# Top_Level.net
KiCad netlist of a schematic drawn in Altium Designer
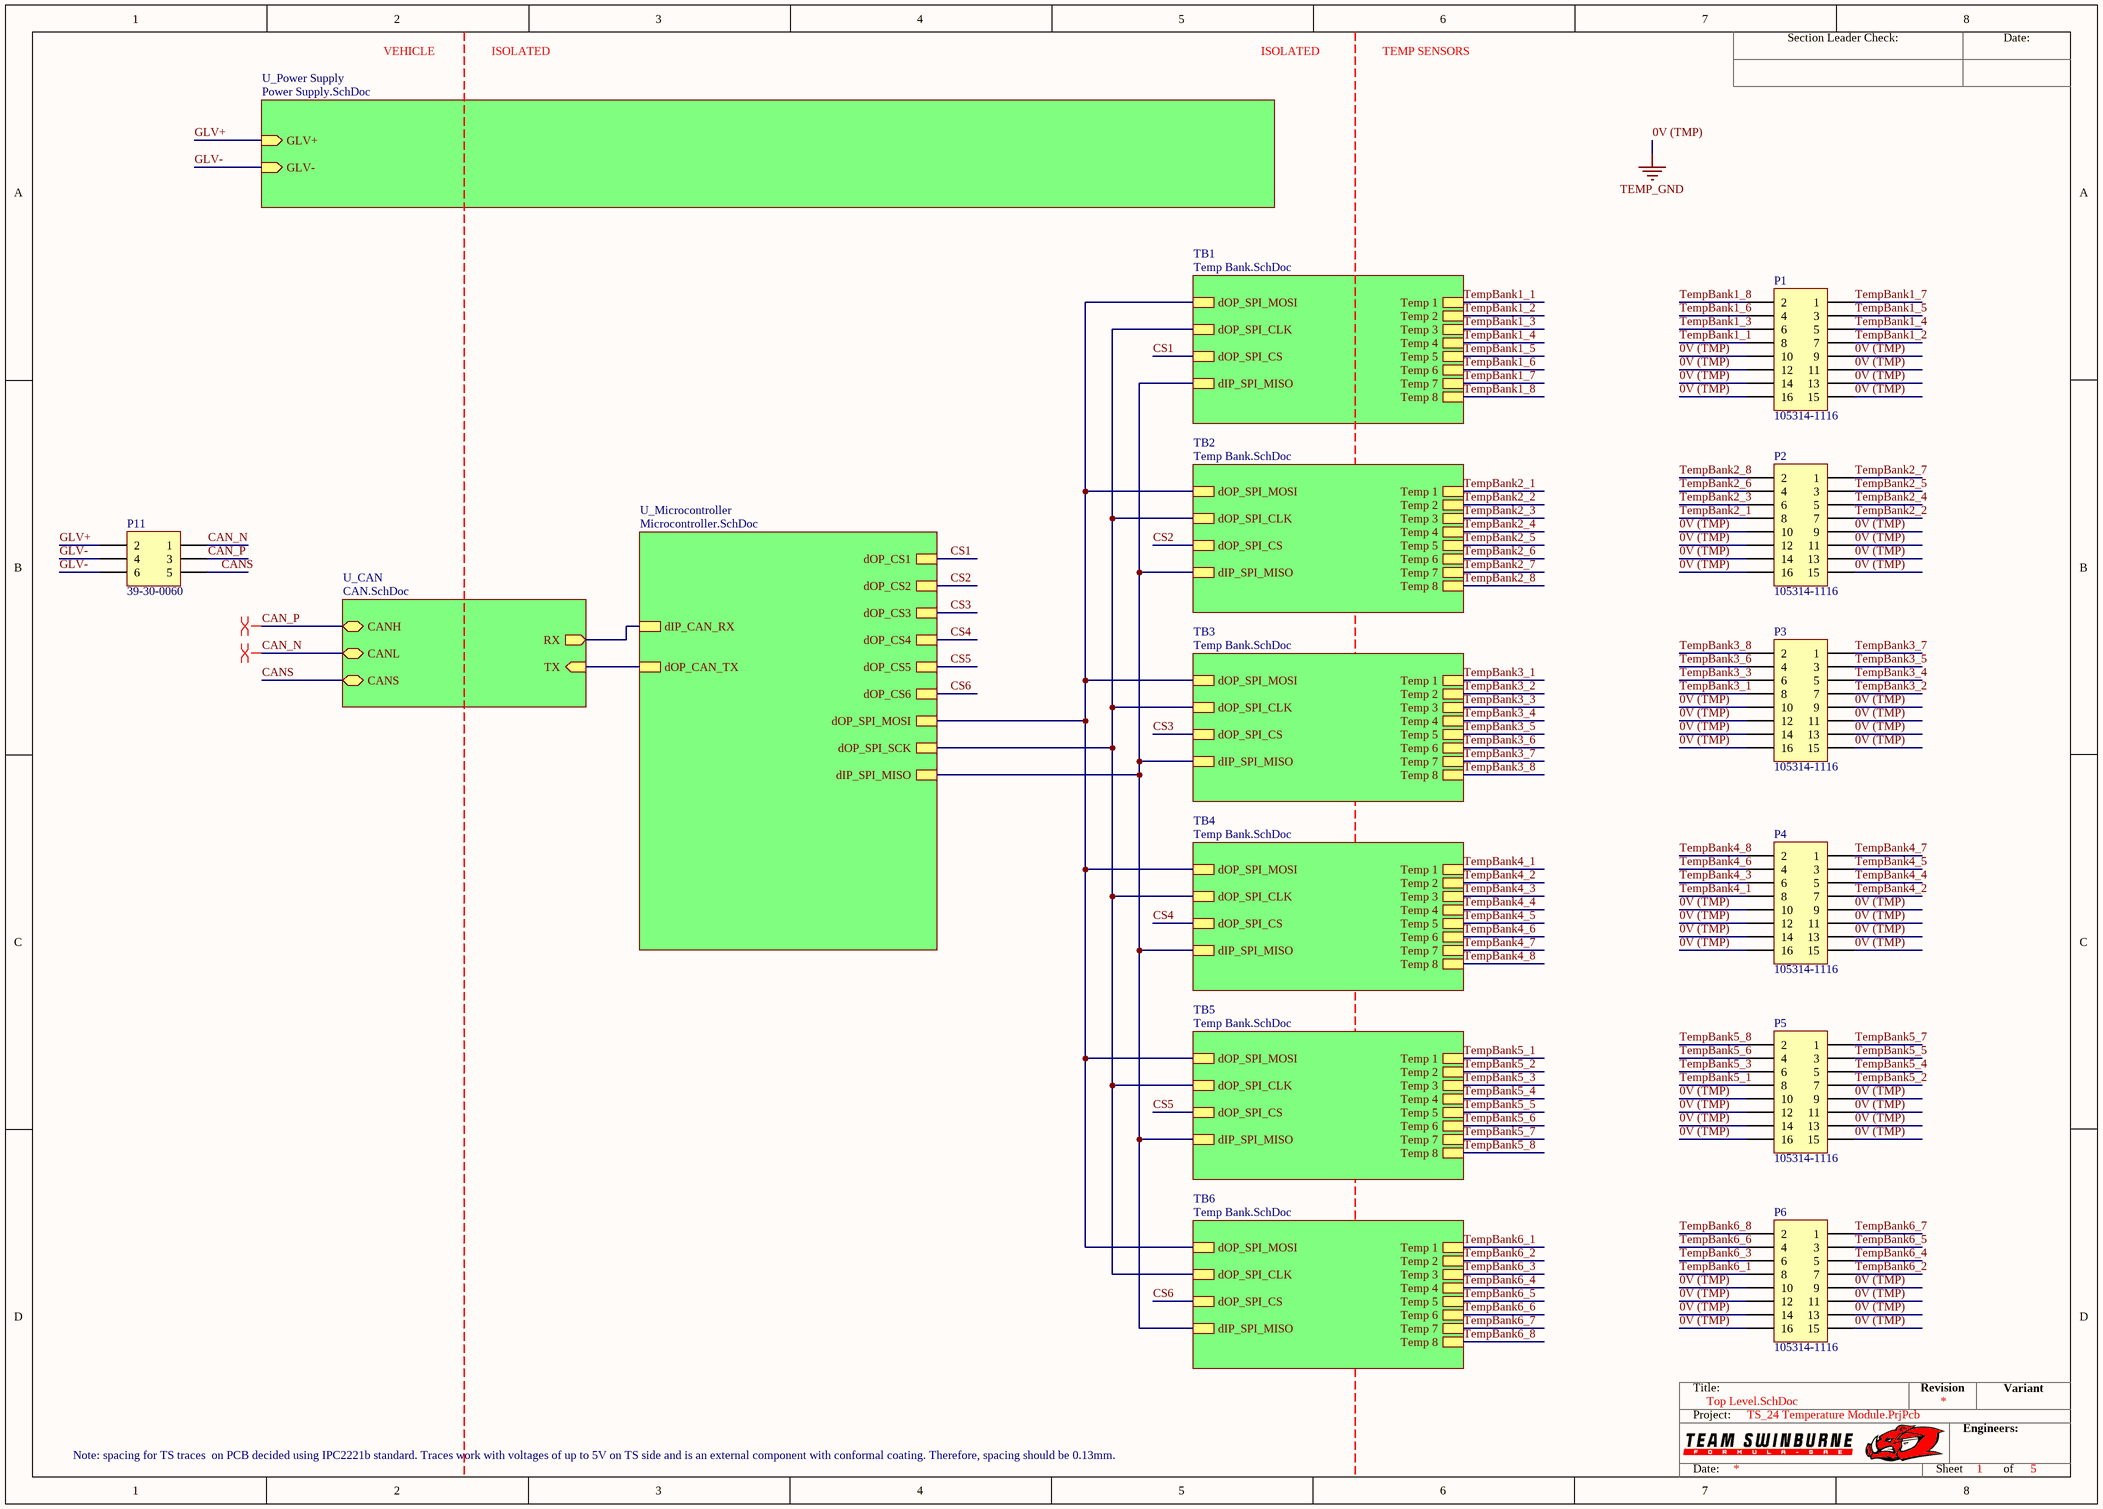
[diagram p0: Top Level.SchDoc]

(export (version "E")
  (design (tool "Eeschema 10.0.6"))
  (components
    (comp (ref "P1")
      (value "105314-1116")
      (footprint "105314-1116-Footprint-1")
      (description "Conn Wire to Board HDR 16 POS 2.5mm Solder RA Side Entry Thru-Hole Tray")
      (libsource (lib "Team Swinburne") (part "105314-1116"))
    )
    (comp (ref "P2")
      (value "105314-1116")
      (footprint "105314-1116-Footprint-1")
      (description "Conn Wire to Board HDR 16 POS 2.5mm Solder RA Side Entry Thru-Hole Tray")
      (libsource (lib "Team Swinburne") (part "105314-1116"))
    )
    (comp (ref "P3")
      (value "105314-1116")
      (footprint "105314-1116-Footprint-1")
      (description "Conn Wire to Board HDR 16 POS 2.5mm Solder RA Side Entry Thru-Hole Tray")
      (libsource (lib "Team Swinburne") (part "105314-1116"))
    )
    (comp (ref "P4")
      (value "105314-1116")
      (footprint "105314-1116-Footprint-1")
      (description "Conn Wire to Board HDR 16 POS 2.5mm Solder RA Side Entry Thru-Hole Tray")
      (libsource (lib "Team Swinburne") (part "105314-1116"))
    )
    (comp (ref "P5")
      (value "105314-1116")
      (footprint "105314-1116-Footprint-1")
      (description "Conn Wire to Board HDR 16 POS 2.5mm Solder RA Side Entry Thru-Hole Tray")
      (libsource (lib "Team Swinburne") (part "105314-1116"))
    )
    (comp (ref "P6")
      (value "105314-1116")
      (footprint "105314-1116-Footprint-1")
      (description "Conn Wire to Board HDR 16 POS 2.5mm Solder RA Side Entry Thru-Hole Tray")
      (libsource (lib "Team Swinburne") (part "105314-1116"))
    )
    (comp (ref "P11")
      (value "39-30-0060")
      (footprint "39-30-0060-Footprint-1")
      (description "Rectangular Power Connector, 6 Contact(s), Male, Solder Terminal, Plug")
      (libsource (lib "Team Swinburne") (part "39-30-0060"))
    )
  )
  (nets
    (net (code "2") (name "/CANS") (class "Default")
      (node (ref "P11") (pin "5") (pinfunction "5_5") (pintype "passive"))
    )
    (net (code "3") (name "/CAN_N") (class "Default")
      (node (ref "P11") (pin "1") (pinfunction "1_1") (pintype "passive"))
    )
    (net (code "4") (name "/CAN_P") (class "Default")
      (node (ref "P11") (pin "3") (pinfunction "3_3") (pintype "passive"))
    )
    (net (code "11") (name "/GLV+") (class "Default")
      (node (ref "P11") (pin "2") (pinfunction "2_2") (pintype "passive"))
    )
    (net (code "12") (name "/GLV-") (class "Default")
      (node (ref "P11") (pin "4") (pinfunction "4_4") (pintype "passive"))
      (node (ref "P11") (pin "6") (pinfunction "6_6") (pintype "passive"))
    )
    (net (code "15") (name "/TempBank1_1") (class "Default")
      (node (ref "P1") (pin "8") (pinfunction "8_8") (pintype "passive"))
    )
    (net (code "16") (name "/TempBank1_2") (class "Default")
      (node (ref "P1") (pin "7") (pinfunction "7_7") (pintype "passive"))
    )
    (net (code "17") (name "/TempBank1_3") (class "Default")
      (node (ref "P1") (pin "6") (pinfunction "6_6") (pintype "passive"))
    )
    (net (code "18") (name "/TempBank1_4") (class "Default")
      (node (ref "P1") (pin "5") (pinfunction "5_5") (pintype "passive"))
    )
    (net (code "19") (name "/TempBank1_5") (class "Default")
      (node (ref "P1") (pin "3") (pinfunction "3_3") (pintype "passive"))
    )
    (net (code "20") (name "/TempBank1_6") (class "Default")
      (node (ref "P1") (pin "4") (pinfunction "4_4") (pintype "passive"))
    )
    (net (code "21") (name "/TempBank1_7") (class "Default")
      (node (ref "P1") (pin "1") (pinfunction "1_1") (pintype "passive"))
    )
    (net (code "22") (name "/TempBank1_8") (class "Default")
      (node (ref "P1") (pin "2") (pinfunction "2_2") (pintype "passive"))
    )
    (net (code "23") (name "/TempBank2_1") (class "Default")
      (node (ref "P2") (pin "8") (pinfunction "8_8") (pintype "passive"))
    )
    (net (code "24") (name "/TempBank2_2") (class "Default")
      (node (ref "P2") (pin "7") (pinfunction "7_7") (pintype "passive"))
    )
    (net (code "25") (name "/TempBank2_3") (class "Default")
      (node (ref "P2") (pin "6") (pinfunction "6_6") (pintype "passive"))
    )
    (net (code "26") (name "/TempBank2_4") (class "Default")
      (node (ref "P2") (pin "5") (pinfunction "5_5") (pintype "passive"))
    )
    (net (code "27") (name "/TempBank2_5") (class "Default")
      (node (ref "P2") (pin "3") (pinfunction "3_3") (pintype "passive"))
    )
    (net (code "28") (name "/TempBank2_6") (class "Default")
      (node (ref "P2") (pin "4") (pinfunction "4_4") (pintype "passive"))
    )
    (net (code "29") (name "/TempBank2_7") (class "Default")
      (node (ref "P2") (pin "1") (pinfunction "1_1") (pintype "passive"))
    )
    (net (code "30") (name "/TempBank2_8") (class "Default")
      (node (ref "P2") (pin "2") (pinfunction "2_2") (pintype "passive"))
    )
    (net (code "31") (name "/TempBank3_1") (class "Default")
      (node (ref "P3") (pin "8") (pinfunction "8_8") (pintype "passive"))
    )
    (net (code "32") (name "/TempBank3_2") (class "Default")
      (node (ref "P3") (pin "7") (pinfunction "7_7") (pintype "passive"))
    )
    (net (code "33") (name "/TempBank3_3") (class "Default")
      (node (ref "P3") (pin "6") (pinfunction "6_6") (pintype "passive"))
    )
    (net (code "34") (name "/TempBank3_4") (class "Default")
      (node (ref "P3") (pin "5") (pinfunction "5_5") (pintype "passive"))
    )
    (net (code "35") (name "/TempBank3_5") (class "Default")
      (node (ref "P3") (pin "3") (pinfunction "3_3") (pintype "passive"))
    )
    (net (code "36") (name "/TempBank3_6") (class "Default")
      (node (ref "P3") (pin "4") (pinfunction "4_4") (pintype "passive"))
    )
    (net (code "37") (name "/TempBank3_7") (class "Default")
      (node (ref "P3") (pin "1") (pinfunction "1_1") (pintype "passive"))
    )
    (net (code "38") (name "/TempBank3_8") (class "Default")
      (node (ref "P3") (pin "2") (pinfunction "2_2") (pintype "passive"))
    )
    (net (code "39") (name "/TempBank4_1") (class "Default")
      (node (ref "P4") (pin "8") (pinfunction "8_8") (pintype "passive"))
    )
    (net (code "40") (name "/TempBank4_2") (class "Default")
      (node (ref "P4") (pin "7") (pinfunction "7_7") (pintype "passive"))
    )
    (net (code "41") (name "/TempBank4_3") (class "Default")
      (node (ref "P4") (pin "6") (pinfunction "6_6") (pintype "passive"))
    )
    (net (code "42") (name "/TempBank4_4") (class "Default")
      (node (ref "P4") (pin "5") (pinfunction "5_5") (pintype "passive"))
    )
    (net (code "43") (name "/TempBank4_5") (class "Default")
      (node (ref "P4") (pin "3") (pinfunction "3_3") (pintype "passive"))
    )
    (net (code "44") (name "/TempBank4_6") (class "Default")
      (node (ref "P4") (pin "4") (pinfunction "4_4") (pintype "passive"))
    )
    (net (code "45") (name "/TempBank4_7") (class "Default")
      (node (ref "P4") (pin "1") (pinfunction "1_1") (pintype "passive"))
    )
    (net (code "46") (name "/TempBank4_8") (class "Default")
      (node (ref "P4") (pin "2") (pinfunction "2_2") (pintype "passive"))
    )
    (net (code "47") (name "/TempBank5_1") (class "Default")
      (node (ref "P5") (pin "8") (pinfunction "8_8") (pintype "passive"))
    )
    (net (code "48") (name "/TempBank5_2") (class "Default")
      (node (ref "P5") (pin "7") (pinfunction "7_7") (pintype "passive"))
    )
    (net (code "49") (name "/TempBank5_3") (class "Default")
      (node (ref "P5") (pin "6") (pinfunction "6_6") (pintype "passive"))
    )
    (net (code "50") (name "/TempBank5_4") (class "Default")
      (node (ref "P5") (pin "5") (pinfunction "5_5") (pintype "passive"))
    )
    (net (code "51") (name "/TempBank5_5") (class "Default")
      (node (ref "P5") (pin "3") (pinfunction "3_3") (pintype "passive"))
    )
    (net (code "52") (name "/TempBank5_6") (class "Default")
      (node (ref "P5") (pin "4") (pinfunction "4_4") (pintype "passive"))
    )
    (net (code "53") (name "/TempBank5_7") (class "Default")
      (node (ref "P5") (pin "1") (pinfunction "1_1") (pintype "passive"))
    )
    (net (code "54") (name "/TempBank5_8") (class "Default")
      (node (ref "P5") (pin "2") (pinfunction "2_2") (pintype "passive"))
    )
    (net (code "55") (name "/TempBank6_1") (class "Default")
      (node (ref "P6") (pin "8") (pinfunction "8_8") (pintype "passive"))
    )
    (net (code "56") (name "/TempBank6_2") (class "Default")
      (node (ref "P6") (pin "7") (pinfunction "7_7") (pintype "passive"))
    )
    (net (code "57") (name "/TempBank6_3") (class "Default")
      (node (ref "P6") (pin "6") (pinfunction "6_6") (pintype "passive"))
    )
    (net (code "58") (name "/TempBank6_4") (class "Default")
      (node (ref "P6") (pin "5") (pinfunction "5_5") (pintype "passive"))
    )
    (net (code "59") (name "/TempBank6_5") (class "Default")
      (node (ref "P6") (pin "3") (pinfunction "3_3") (pintype "passive"))
    )
    (net (code "60") (name "/TempBank6_6") (class "Default")
      (node (ref "P6") (pin "4") (pinfunction "4_4") (pintype "passive"))
    )
    (net (code "61") (name "/TempBank6_7") (class "Default")
      (node (ref "P6") (pin "1") (pinfunction "1_1") (pintype "passive"))
    )
    (net (code "62") (name "/TempBank6_8") (class "Default")
      (node (ref "P6") (pin "2") (pinfunction "2_2") (pintype "passive"))
    )
    (net (code "66") (name "TEMP_GND") (class "Default")
      (node (ref "P1") (pin "10") (pinfunction "10_10") (pintype "passive"))
      (node (ref "P1") (pin "11") (pinfunction "11_11") (pintype "passive"))
      (node (ref "P1") (pin "12") (pinfunction "12_12") (pintype "passive"))
      (node (ref "P1") (pin "13") (pinfunction "13_13") (pintype "passive"))
      (node (ref "P1") (pin "14") (pinfunction "14_14") (pintype "passive"))
      (node (ref "P1") (pin "15") (pinfunction "15_15") (pintype "passive"))
      (node (ref "P1") (pin "16") (pinfunction "16_16") (pintype "passive"))
      (node (ref "P1") (pin "9") (pinfunction "9_9") (pintype "passive"))
      (node (ref "P2") (pin "10") (pinfunction "10_10") (pintype "passive"))
      (node (ref "P2") (pin "11") (pinfunction "11_11") (pintype "passive"))
      (node (ref "P2") (pin "12") (pinfunction "12_12") (pintype "passive"))
      (node (ref "P2") (pin "13") (pinfunction "13_13") (pintype "passive"))
      (node (ref "P2") (pin "14") (pinfunction "14_14") (pintype "passive"))
      (node (ref "P2") (pin "15") (pinfunction "15_15") (pintype "passive"))
      (node (ref "P2") (pin "16") (pinfunction "16_16") (pintype "passive"))
      (node (ref "P2") (pin "9") (pinfunction "9_9") (pintype "passive"))
      (node (ref "P3") (pin "10") (pinfunction "10_10") (pintype "passive"))
      (node (ref "P3") (pin "11") (pinfunction "11_11") (pintype "passive"))
      (node (ref "P3") (pin "12") (pinfunction "12_12") (pintype "passive"))
      (node (ref "P3") (pin "13") (pinfunction "13_13") (pintype "passive"))
      (node (ref "P3") (pin "14") (pinfunction "14_14") (pintype "passive"))
      (node (ref "P3") (pin "15") (pinfunction "15_15") (pintype "passive"))
      (node (ref "P3") (pin "16") (pinfunction "16_16") (pintype "passive"))
      (node (ref "P3") (pin "9") (pinfunction "9_9") (pintype "passive"))
      (node (ref "P4") (pin "10") (pinfunction "10_10") (pintype "passive"))
      (node (ref "P4") (pin "11") (pinfunction "11_11") (pintype "passive"))
      (node (ref "P4") (pin "12") (pinfunction "12_12") (pintype "passive"))
      (node (ref "P4") (pin "13") (pinfunction "13_13") (pintype "passive"))
      (node (ref "P4") (pin "14") (pinfunction "14_14") (pintype "passive"))
      (node (ref "P4") (pin "15") (pinfunction "15_15") (pintype "passive"))
      (node (ref "P4") (pin "16") (pinfunction "16_16") (pintype "passive"))
      (node (ref "P4") (pin "9") (pinfunction "9_9") (pintype "passive"))
      (node (ref "P5") (pin "10") (pinfunction "10_10") (pintype "passive"))
      (node (ref "P5") (pin "11") (pinfunction "11_11") (pintype "passive"))
      (node (ref "P5") (pin "12") (pinfunction "12_12") (pintype "passive"))
      (node (ref "P5") (pin "13") (pinfunction "13_13") (pintype "passive"))
      (node (ref "P5") (pin "14") (pinfunction "14_14") (pintype "passive"))
      (node (ref "P5") (pin "15") (pinfunction "15_15") (pintype "passive"))
      (node (ref "P5") (pin "16") (pinfunction "16_16") (pintype "passive"))
      (node (ref "P5") (pin "9") (pinfunction "9_9") (pintype "passive"))
      (node (ref "P6") (pin "10") (pinfunction "10_10") (pintype "passive"))
      (node (ref "P6") (pin "11") (pinfunction "11_11") (pintype "passive"))
      (node (ref "P6") (pin "12") (pinfunction "12_12") (pintype "passive"))
      (node (ref "P6") (pin "13") (pinfunction "13_13") (pintype "passive"))
      (node (ref "P6") (pin "14") (pinfunction "14_14") (pintype "passive"))
      (node (ref "P6") (pin "15") (pinfunction "15_15") (pintype "passive"))
      (node (ref "P6") (pin "16") (pinfunction "16_16") (pintype "passive"))
      (node (ref "P6") (pin "9") (pinfunction "9_9") (pintype "passive"))
    )
  )
)
